# Output.net
KiCad netlist of a schematic drawn in Altium Designer
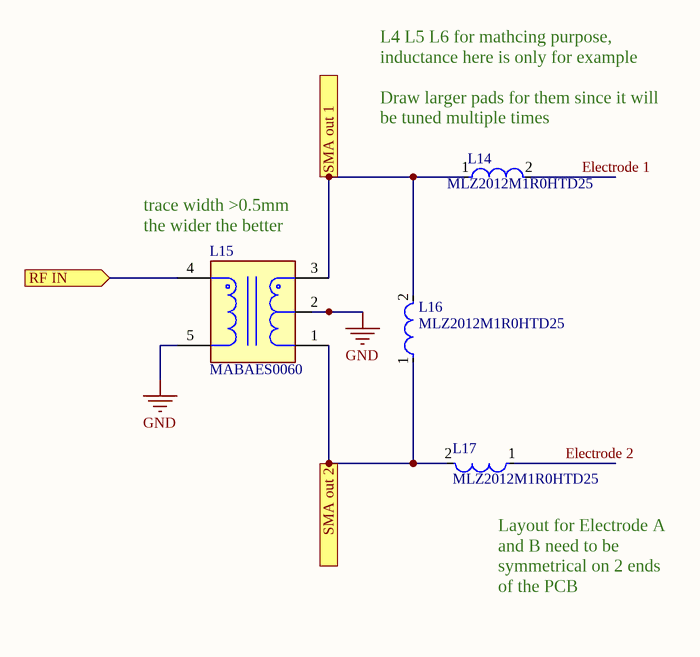
[diagram p0: Output.SchDoc]

(export (version "E")
  (design (tool "Eeschema 10.0.6"))
  (components
    (comp (ref "L14")
      (value "MLZ2012M1R0HTD25")
      (footprint "FP-MLZ2012-1_25-IPC_C")
      (description "Shielded Multilayer Inductor 1uH ±20% 800mA 130mΩ AEC-Q200 SMD 0805")
      (fields (field (name "TOLERANCE") "20%"))
      (libsource (lib "Altium Content Vault") (part "725321dda6339637d4d059423bc1c3c"))
    )
    (comp (ref "L15")
      (value "MABAES0060")
      (footprint "FP-MABAES0060-MFG")
      (description "BALUN 300KHZ-200MHZ 1:1 6SMD")
      (libsource (lib "Altium Content Vault") (part "a416973d4767a0660ebfda87df8877f"))
    )
    (comp (ref "L16")
      (value "MLZ2012M1R0HTD25")
      (footprint "FP-MLZ2012-1_25-IPC_C")
      (description "Shielded Multilayer Inductor 1uH ±20% 800mA 130mΩ AEC-Q200 SMD 0805")
      (fields (field (name "TOLERANCE") "20%"))
      (libsource (lib "Altium Content Vault") (part "725321dda6339637d4d059423bc1c3c"))
    )
    (comp (ref "L17")
      (value "MLZ2012M1R0HTD25")
      (footprint "FP-MLZ2012-1_25-IPC_C")
      (description "Shielded Multilayer Inductor 1uH ±20% 800mA 130mΩ AEC-Q200 SMD 0805")
      (fields (field (name "TOLERANCE") "20%"))
      (libsource (lib "Altium Content Vault") (part "725321dda6339637d4d059423bc1c3c"))
    )
  )
  (nets
    (net (code "1") (name "/Electrode 1") (class "Default")
      (node (ref "L14") (pin "2") (pinfunction "2_2") (pintype "passive"))
    )
    (net (code "2") (name "/Electrode 2") (class "Default")
      (node (ref "L17") (pin "1") (pinfunction "1_1") (pintype "passive"))
    )
    (net (code "3") (name "/RF IN") (class "Default")
      (node (ref "L15") (pin "4") (pinfunction "Primary_dot_4") (pintype "passive"))
    )
    (net (code "4") (name "/SMA out 1") (class "Default")
      (node (ref "L14") (pin "1") (pinfunction "1_1") (pintype "passive"))
      (node (ref "L15") (pin "3") (pinfunction "Secondary_Dot_3") (pintype "passive"))
      (node (ref "L16") (pin "2") (pinfunction "2_2") (pintype "passive"))
    )
    (net (code "5") (name "/SMA out 2") (class "Default")
      (node (ref "L15") (pin "1") (pinfunction "Secondary_1") (pintype "passive"))
      (node (ref "L16") (pin "1") (pinfunction "1_1") (pintype "passive"))
      (node (ref "L17") (pin "2") (pinfunction "2_2") (pintype "passive"))
    )
    (net (code "6") (name "GND") (class "Default")
      (node (ref "L15") (pin "2") (pinfunction "Secondary_CT_2") (pintype "passive"))
      (node (ref "L15") (pin "5") (pinfunction "Primary_5") (pintype "passive"))
    )
  )
)
